# 4_High_Voltage.net
KiCad netlist of a schematic drawn in Altium Designer
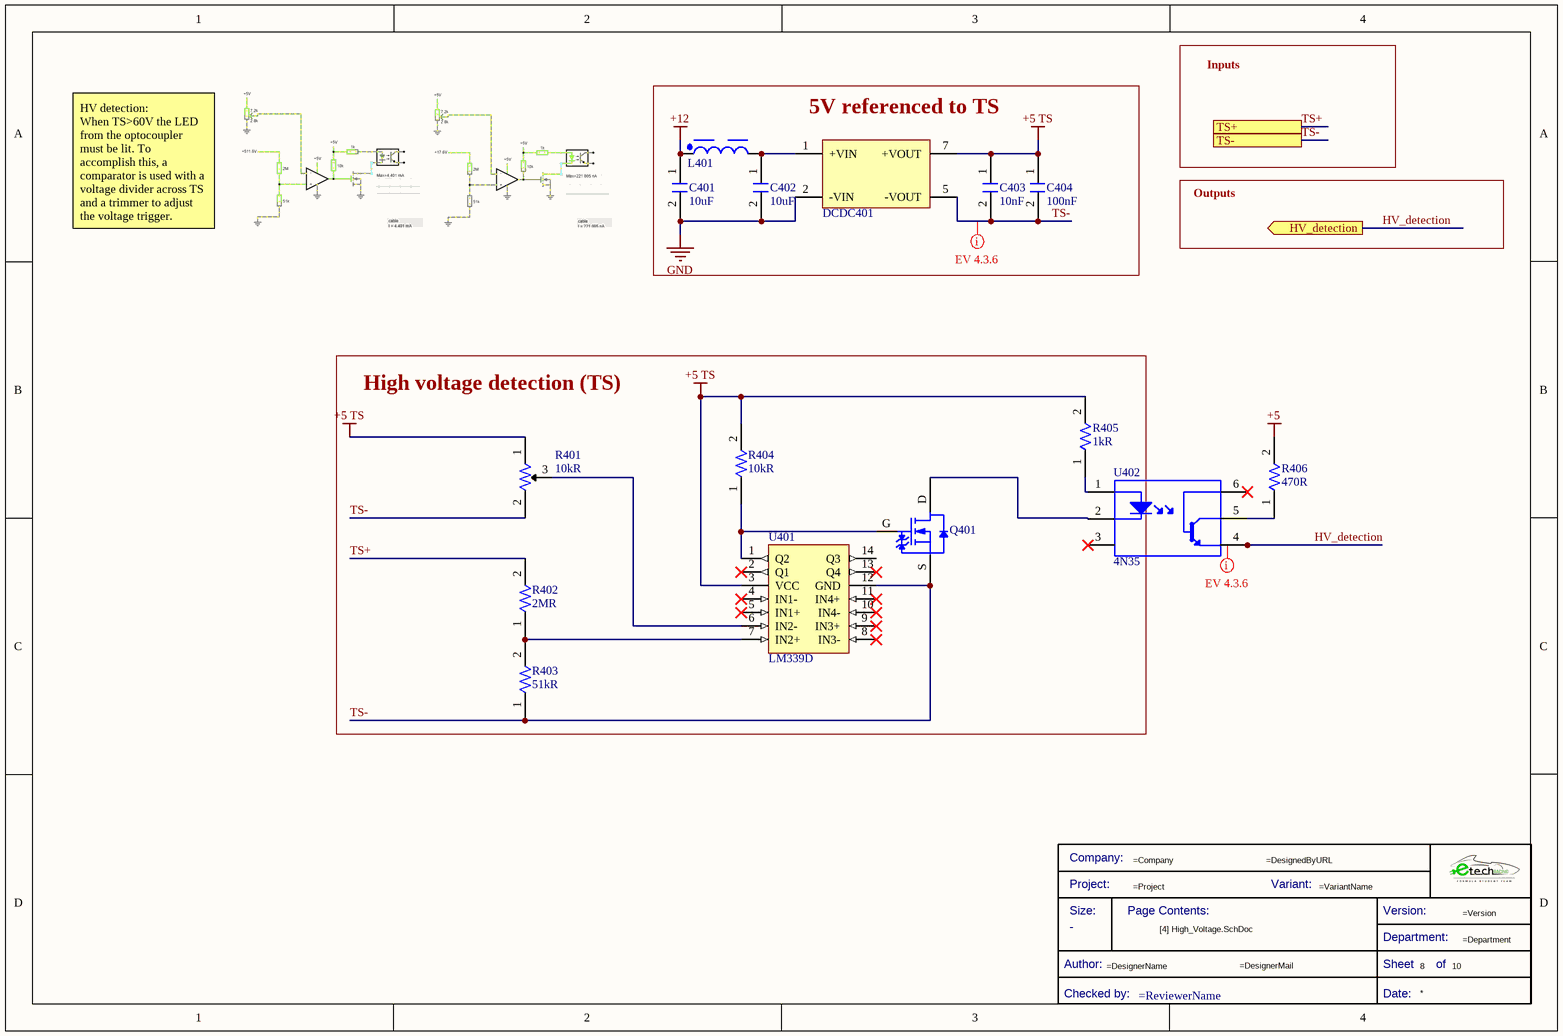
[diagram p0: [4] High_Voltage.SchDoc]

(export (version "E")
  (design (tool "Eeschema 10.0.6"))
  (components
    (comp (ref "*")
      (value "Title Block_template")
      (description "Standard Title Block")
      (fields (field (name "SIZE") "-"))
      (libsource (lib "e-Tech_Racing") (part "Title Block_template"))
    )
    (comp (ref "C401")
      (value "GRJ32ER71H106KE11L")
      (footprint "C10u-50V-1210FNPMLCC-X7R")
      (description "Multilayer Ceramic Capacitors MLCC - SMD/SMT 1210 10uF 50volts X7R +/-10% Soft Term")
      (fields
        (field (name "MANUFACTURER") "Murata")
        (field (name "TOLERANCE") "10%")
        (field (name "CAPACITANCE") "10uF")
        (field (name ".CREATOR") "DR")
      )
      (libsource (lib "Passives") (part "C10u-50V-1210FNPMLCC-X7R"))
    )
    (comp (ref "C402")
      (value "GRJ32ER71H106KE11L")
      (footprint "C10u-50V-1210FNPMLCC-X7R")
      (description "Multilayer Ceramic Capacitors MLCC - SMD/SMT 1210 10uF 50volts X7R +/-10% Soft Term")
      (fields
        (field (name "MANUFACTURER") "Murata")
        (field (name "TOLERANCE") "10%")
        (field (name "CAPACITANCE") "10uF")
        (field (name ".CREATOR") "DR")
      )
      (libsource (lib "Passives") (part "C10u-50V-1210FNPMLCC-X7R"))
    )
    (comp (ref "C403")
      (value "885012207092")
      (footprint "C0805FNPC-R")
      (description "Cap, 0.01ΜF, 50V, 10%, X7R, 0805")
      (fields
        (field (name "TOLERANCE") "10%")
        (field (name "CAPACITANCE") "10nF")
        (field (name ".CREATOR") "DR")
      )
      (libsource (lib "Passives") (part "C10n-50V-0805FNPC-X7R"))
    )
    (comp (ref "C404")
      (value "885012207098")
      (footprint "C0805FNPC-R")
      (description "Cap, 0.1ΜF, 50V, 10%, X7R, 0805")
      (fields
        (field (name "TOLERANCE") "10%")
        (field (name "CAPACITANCE") "100nF")
        (field (name ".CREATOR") "DR")
      )
      (libsource (lib "Passives") (part "C100n-50V-0805FNPC-X7R"))
    )
    (comp (ref "DCDC401")
      (value "1779405241")
      (footprint "DCDC2W-ISO/1779405X41")
      (description "WPME-FISM Fixed Isolated Module, SIP-7, 10.8-13.2Vin, 5Vout")
      (fields (field (name "MANUFACTURER") "Wurth Elektronik"))
      (libsource (lib "Semiconductor") (part "DCDC-ISO-2W/12V/5V"))
    )
    (comp (ref "L401")
      (value "744042470")
      (footprint "L_Power_ 47uH")
      (description "WE-TPC SMT Tiny Power Inductor, size 4818, 47uH, 0.62A, 540mOhm")
      (fields (field (name "MANUFACTURER") "Wurth Elektronik"))
      (libsource (lib "Passives") (part "L_47uH_0.6A"))
    )
    (comp (ref "Q401")
      (value "SQ2318BES-T1_GE3")
      (footprint "TRT-NCH-3/35-CPH")
      (description "Automotive N-channel 40 V (d-s) 175C Mosfet SOT-23")
      (fields (field (name ".CREATOR") "DO"))
      (libsource (lib "Semiconductor") (part "TRT-NCH-8/40-SQ"))
    )
    (comp (ref "R401")
      (value "3296W-1-103LF")
      (footprint "R10k-VTR")
      (description "Trimmer, Cermet, Rest 10 Kilohms, PCB, 25 Turns, Pwr-Rtg 0.5W, 3296 Series")
      (fields
        (field (name "MANUFACTURER") "Bourns")
        (field (name "TOLERANCE") "10%")
        (field (name "RESISTANCE") "10kR")
        (field (name ".CREATOR") "DO")
      )
      (libsource (lib "Passives") (part "R10k-VTR"))
    )
    (comp (ref "R402")
      (value "R2M-2512FTK")
      (footprint "R2512FTK")
      (description "Current Sense Resistors - SMD 3watts .002ohms 1%")
      (fields
        (field (name "MANUFACTURER") "Vishay Dale")
        (field (name "MANUFACTURER PART NUMBER") "WSLP25122L000FEA")
        (field (name "RESISTANCE") "2MR")
      )
      (libsource (lib "Passives") (part "R2M-2512FTK"))
    )
    (comp (ref "R403")
      (value "CRCW120610K0FKEA")
      (footprint "R1206FTK-W")
      (description "Res Thick Film 1206 51K Ohm 1% 1/4W ±100ppm/°C Molded SMD SMD Punched Carrier T/R")
      (fields
        (field (name "MANUFACTURER") "Panasonic")
        (field (name "MANUFACTURER PART NUMBER") "ERJ-S08F5102V")
        (field (name "RESISTANCE") "51kR")
        (field (name ".CREATOR") "DO")
      )
      (libsource (lib "Passives") (part "R51k-1206FTK"))
    )
    (comp (ref "R404")
      (value "CR0805-JW-103ELF")
      (footprint "R0805FTK")
      (fields
        (field (name "TOLERANCE") "5%")
        (field (name "RESISTANCE") "10kR")
        (field (name ".CREATOR") "DR")
      )
      (libsource (lib "Passives") (part "R10k-0805FTK"))
    )
    (comp (ref "R405")
      (value "CR0805-JW-102ELF")
      (footprint "R0805FTK")
      (description "Res Thick Film 0805 1K Ohm 5% 1/8W ±200ppm/°C Molded SMD SMD Paper Tape on Plastic Reel")
      (fields
        (field (name "TOLERANCE") "5%")
        (field (name "RESISTANCE") "1kR")
        (field (name ".CREATOR") "GP")
      )
      (libsource (lib "Passives") (part "R1k-0805FTK"))
    )
    (comp (ref "R406")
      (value "CR0805-FX-4700GLF")
      (footprint "R0805FTK")
      (description "Res Thick Film 0805 470 Ohm 1% 1/8W ±100ppm/°C Molded SMD SMD Paper Tape on Plastic Reel")
      (fields
        (field (name "TOLERANCE") "1%")
        (field (name "RESISTANCE") "470R")
        (field (name ".CREATOR") "DR")
      )
      (libsource (lib "Passives") (part "R470-0805FTK"))
    )
    (comp (ref "U401")
      (value "LM339D")
      (footprint "Array_4_Amp_LM339D")
      (description "Comparator Quad ±18V/36V 14-Pin SOIC Tube")
      (fields
        (field (name "MANUFACTURER") "Texas Instruments")
        (field (name "MANUFACTURER PART NUMBER") "LM339D")
        (field (name ".CREATOR") "DO")
      )
      (libsource (lib "Integrated circuits") (part "Array_4_Amp_LM339D"))
    )
    (comp (ref "U402")
      (value "4N35")
      (footprint "Optocoupler_4N35")
      (description "Optocoupler DC-IN 1-CH Transistor With Base DC-OUT 6-Pin PDIP SMD T/R")
      (fields
        (field (name "MANUFACTURER") "Vishay Lite-On")
        (field (name "MANUFACTURER PART NUMBER") "CNY17-4S-TA1")
        (field (name ".CREATOR") "DO")
      )
      (libsource (lib "Semiconductor") (part "Optocoupler_4N35"))
    )
  )
  (nets
    (net (code "1") (name "+5") (class "Default")
      (node (ref "R406") (pin "2") (pinfunction "2_2") (pintype "passive"))
    )
    (net (code "2") (name "+5 TS") (class "Default")
      (node (ref "C403") (pin "1") (pinfunction "1_1") (pintype "passive"))
      (node (ref "C404") (pin "1") (pinfunction "1_1") (pintype "passive"))
      (node (ref "DCDC401") (pin "7") (pinfunction "+VOUT_7") (pintype "passive"))
      (node (ref "R401") (pin "1") (pinfunction "2_1") (pintype "passive"))
      (node (ref "R404") (pin "2") (pinfunction "2_2") (pintype "passive"))
      (node (ref "R405") (pin "2") (pinfunction "2_2") (pintype "passive"))
      (node (ref "U401") (pin "3") (pinfunction "VCC_3") (pintype "power_in"))
    )
    (net (code "3") (name "+12") (class "Default")
      (node (ref "C401") (pin "1") (pinfunction "1_1") (pintype "passive"))
      (node (ref "L401") (pin "1") (pinfunction "1_1") (pintype "passive"))
    )
    (net (code "4") (name "/HV_detection") (class "Default")
      (node (ref "U402") (pin "4") (pinfunction "E_4") (pintype "passive"))
    )
    (net (code "5") (name "/TS+") (class "Default")
      (node (ref "R402") (pin "2") (pinfunction "2_2") (pintype "passive"))
    )
    (net (code "6") (name "/TS-") (class "Default")
      (node (ref "C403") (pin "2") (pinfunction "2_2") (pintype "passive"))
      (node (ref "C404") (pin "2") (pinfunction "2_2") (pintype "passive"))
      (node (ref "DCDC401") (pin "5") (pinfunction "-VOUT_5") (pintype "passive"))
      (node (ref "Q401") (pin "S") (pinfunction "S_S") (pintype "passive"))
      (node (ref "R401") (pin "2") (pinfunction "2_2") (pintype "passive"))
      (node (ref "R403") (pin "1") (pinfunction "1_1") (pintype "passive"))
      (node (ref "U401") (pin "12") (pinfunction "GND_12") (pintype "power_in"))
    )
    (net (code "7") (name "GND") (class "Default")
      (node (ref "C401") (pin "2") (pinfunction "2_2") (pintype "passive"))
      (node (ref "C402") (pin "2") (pinfunction "2_2") (pintype "passive"))
      (node (ref "DCDC401") (pin "2") (pinfunction "-VIN_2") (pintype "passive"))
    )
    (net (code "8") (name "Net-(DCDC401-+VIN)") (class "Default")
      (node (ref "C402") (pin "1") (pinfunction "1_1") (pintype "passive"))
      (node (ref "DCDC401") (pin "1") (pinfunction "+VIN_1") (pintype "passive"))
      (node (ref "L401") (pin "2") (pinfunction "2_2") (pintype "passive"))
    )
    (net (code "9") (name "Net-(R406-Pad1)") (class "Default")
      (node (ref "R406") (pin "1") (pinfunction "1_1") (pintype "passive"))
      (node (ref "U402") (pin "5") (pinfunction "E_5") (pintype "passive"))
    )
    (net (code "10") (name "Net-(U401-IN2+)") (class "Default")
      (node (ref "R402") (pin "1") (pinfunction "1_1") (pintype "passive"))
      (node (ref "R403") (pin "2") (pinfunction "2_2") (pintype "passive"))
      (node (ref "U401") (pin "7") (pinfunction "IN2+_7") (pintype "input"))
    )
    (net (code "11") (name "Net-(U401-IN2-)") (class "Default")
      (node (ref "R401") (pin "3") (pinfunction "3_3") (pintype "passive"))
      (node (ref "U401") (pin "6") (pinfunction "IN2-_6") (pintype "input"))
    )
    (net (code "12") (name "Net-(U401-Q2)") (class "Default")
      (node (ref "Q401") (pin "G") (pinfunction "G_G") (pintype "passive"))
      (node (ref "R404") (pin "1") (pinfunction "1_1") (pintype "passive"))
      (node (ref "U401") (pin "1") (pinfunction "Q2_1") (pintype "output"))
    )
    (net (code "13") (name "Net-(U402-A)") (class "Default")
      (node (ref "R405") (pin "1") (pinfunction "1_1") (pintype "passive"))
      (node (ref "U402") (pin "1") (pinfunction "A_1") (pintype "passive"))
    )
    (net (code "14") (name "Net-(U402-K)") (class "Default")
      (node (ref "Q401") (pin "D") (pinfunction "D_D") (pintype "passive"))
      (node (ref "U402") (pin "2") (pinfunction "K_2") (pintype "passive"))
    )
    (net (code "15") (name "unconnected-(U401-IN1+-Pad5)") (class "Default")
      (node (ref "U401") (pin "5") (pinfunction "IN1+_5") (pintype "input+no_connect"))
    )
    (net (code "16") (name "unconnected-(U401-IN1--Pad4)") (class "Default")
      (node (ref "U401") (pin "4") (pinfunction "IN1-_4") (pintype "input+no_connect"))
    )
    (net (code "17") (name "unconnected-(U401-IN3+-Pad9)") (class "Default")
      (node (ref "U401") (pin "9") (pinfunction "IN3+_9") (pintype "input+no_connect"))
    )
    (net (code "18") (name "unconnected-(U401-IN3--Pad8)") (class "Default")
      (node (ref "U401") (pin "8") (pinfunction "IN3-_8") (pintype "input+no_connect"))
    )
    (net (code "19") (name "unconnected-(U401-IN4+-Pad11)") (class "Default")
      (node (ref "U401") (pin "11") (pinfunction "IN4+_11") (pintype "input+no_connect"))
    )
    (net (code "20") (name "unconnected-(U401-IN4--Pad10)") (class "Default")
      (node (ref "U401") (pin "10") (pinfunction "IN4-_10") (pintype "input+no_connect"))
    )
    (net (code "21") (name "unconnected-(U401-Q1-Pad2)") (class "Default")
      (node (ref "U401") (pin "2") (pinfunction "Q1_2") (pintype "output+no_connect"))
    )
    (net (code "22") (name "unconnected-(U401-Q3-Pad14)") (class "Default")
      (node (ref "U401") (pin "14") (pinfunction "Q3_14") (pintype "output"))
    )
    (net (code "23") (name "unconnected-(U401-Q4-Pad13)") (class "Default")
      (node (ref "U401") (pin "13") (pinfunction "Q4_13") (pintype "output+no_connect"))
    )
    (net (code "24") (name "unconnected-(U402-C-Pad3)") (class "Default")
      (node (ref "U402") (pin "3") (pinfunction "C_3") (pintype "passive+no_connect"))
    )
    (net (code "25") (name "unconnected-(U402-E-Pad6)") (class "Default")
      (node (ref "U402") (pin "6") (pinfunction "E_6") (pintype "passive+no_connect"))
    )
  )
)
